# MAX_M10M_PINOUT.net
KiCad netlist of a schematic drawn in Altium Designer
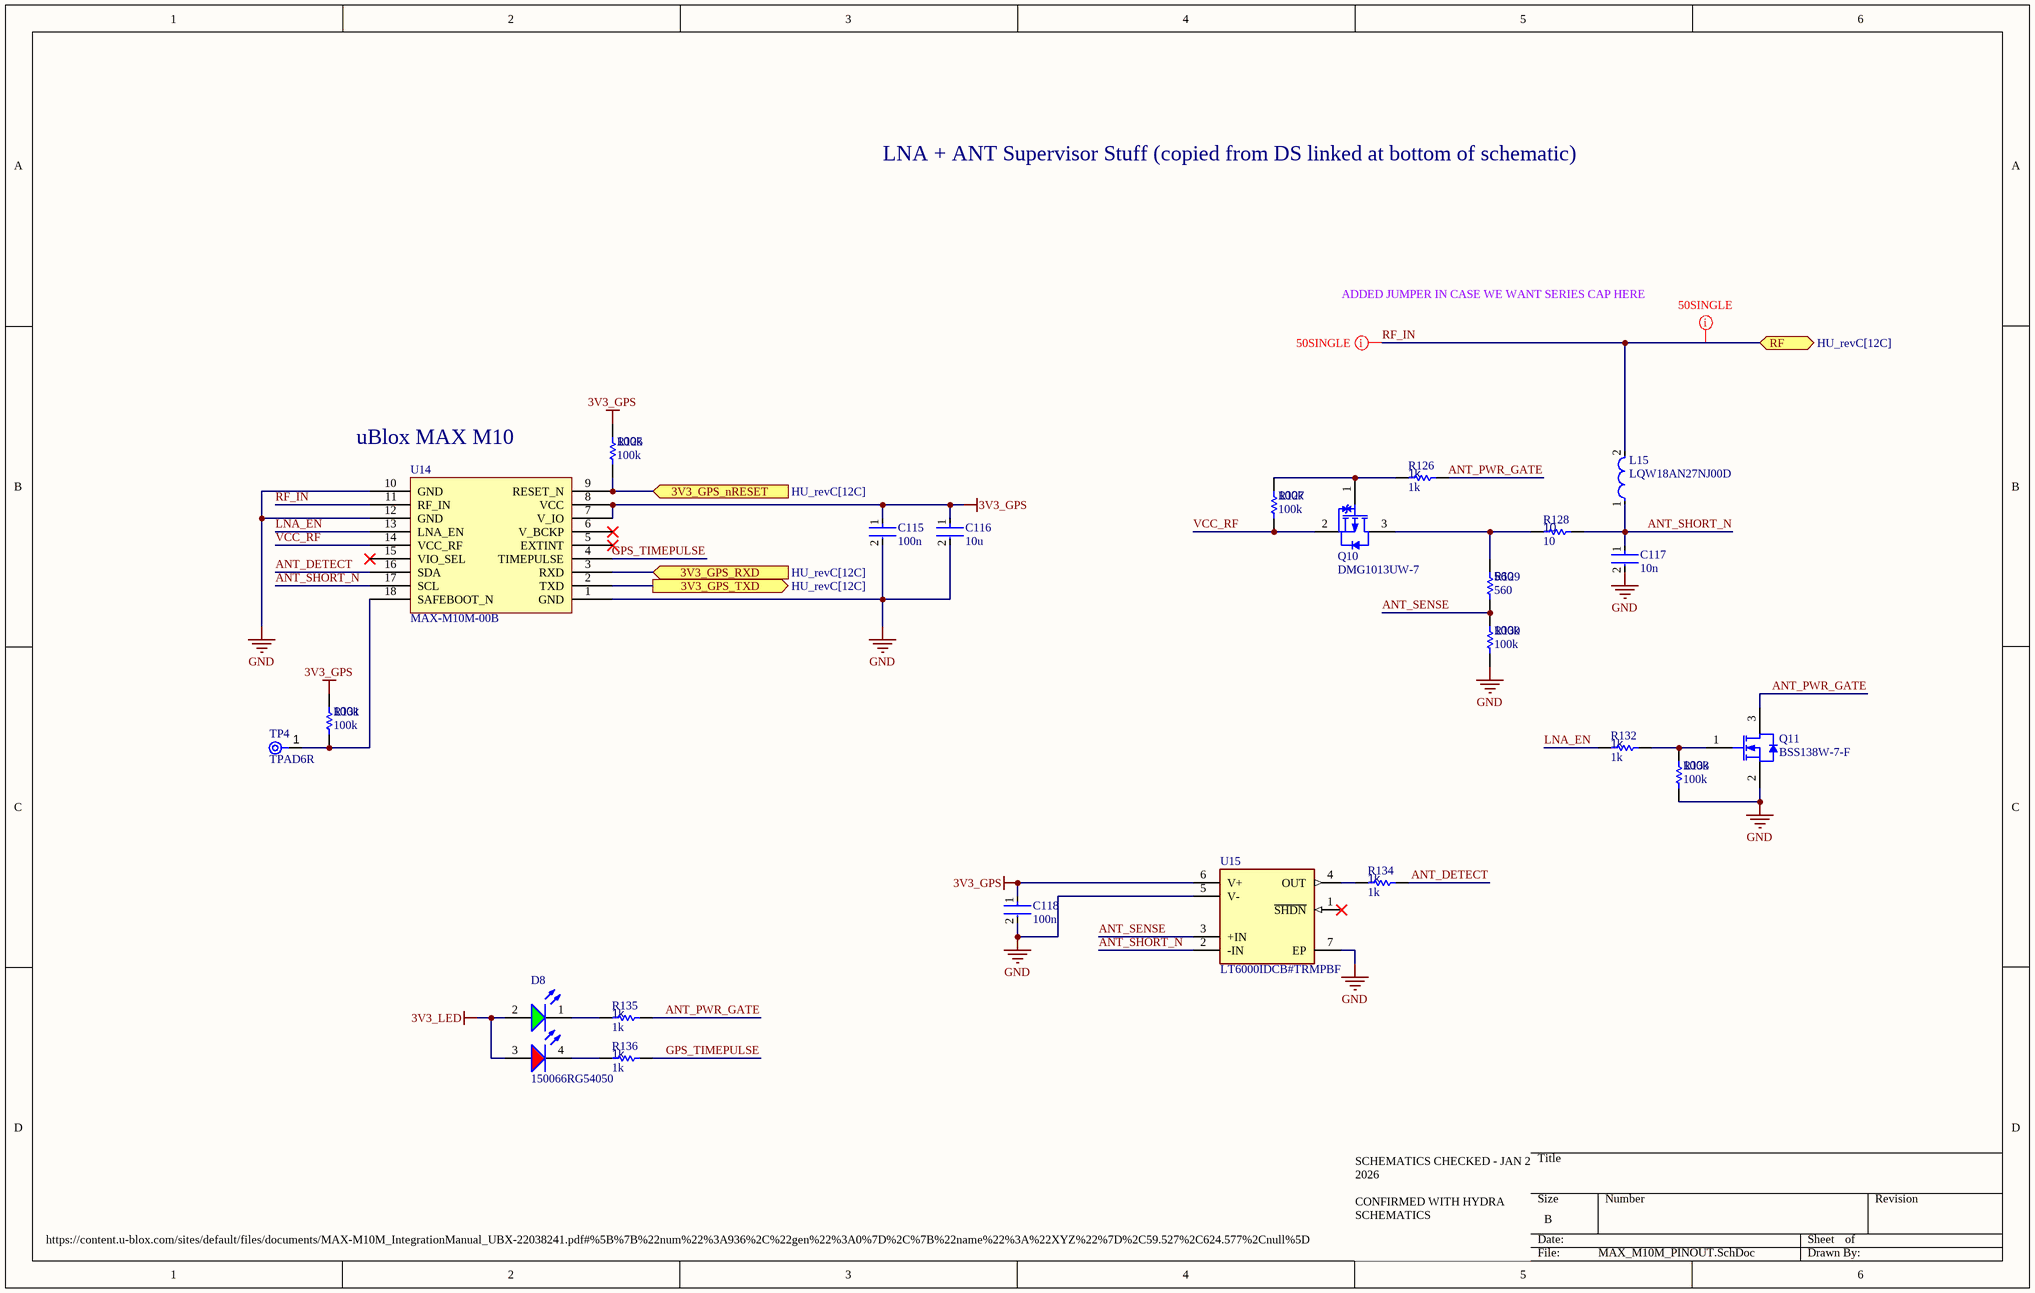
[diagram p0: MAX_M10M_PINOUT.SchDoc]

(export (version "E")
  (design (tool "Eeschema 10.0.6"))
  (components
    (comp (ref "C115")
      (value "100n")
      (footprint "FP-0402-L_1_0_0_05-W_0_5-IPC_A")
      (description "LARGE PADS, 0402 CAP, CHANGE COMMENT TO MATCH REAL P/N")
      (libsource (lib "Space Concordia") (part "b4654b650e69147ec39a6b967a45e02"))
    )
    (comp (ref "C116")
      (value "10u")
      (footprint "FP-0402-L_1_0_0_05-W_0_5-IPC_A")
      (description "LARGE PADS, 0402 CAP, CHANGE COMMENT TO MATCH REAL P/N")
      (libsource (lib "Space Concordia") (part "b4654b650e69147ec39a6b967a45e02"))
    )
    (comp (ref "C117")
      (value "10n")
      (footprint "FP-0402-L_1_0_0_05-W_0_5-IPC_A")
      (description "LARGE PADS, 0402 CAP, CHANGE COMMENT TO MATCH REAL P/N")
      (libsource (lib "Space Concordia") (part "b4654b650e69147ec39a6b967a45e02"))
    )
    (comp (ref "C118")
      (value "100n")
      (footprint "FP-0402-L_1_0_0_05-W_0_5-IPC_A")
      (description "LARGE PADS, 0402 CAP, CHANGE COMMENT TO MATCH REAL P/N")
      (libsource (lib "Space Concordia") (part "b4654b650e69147ec39a6b967a45e02"))
    )
    (comp (ref "D8")
      (value "150066RG54050")
      (footprint "WL-SBCD_0606")
      (description "Led, Red/Grn, 180Mcd/230Mcd, 624Nm/525Nm Rohs Compliant: Yes")
      (fields (field (name "SOURCE") "rgled.SchLib"))
      (libsource (lib "Space Concordia") (part "CMP-004-00034-2"))
    )
    (comp (ref "L15")
      (value "LQW18AN27NJ00D")
      (footprint "FP-LQW18AN_00-MFG")
      (description "Wire Wound RF Inductor 27nH ±5% 440mA 0.21Ω 0603 (1608)")
      (fields (field (name "TOLERANCE") "5%"))
      (libsource (lib "Altium Content Vault") (part "725321dda6339637d4d059423bc1c3c"))
    )
    (comp (ref "Q10")
      (value "DMG1013UW-7")
      (footprint "DIOD-SOT323-3_V")
      (fields (field (name "MANUFACTURER") "Diodes Inc"))
      (libsource (lib "Altium Content Vault") (part "PEMOS-GSD-3_C"))
    )
    (comp (ref "Q11")
      (value "BSS138W-7-F")
      (footprint "DIOD-SOT323-3_V")
      (fields (field (name "MANUFACTURER") "DiodesIncorporated"))
      (libsource (lib "Altium Content Vault") (part "NEMOS-GSD-3"))
    )
    (comp (ref "R125")
      (value "100k")
      (footprint "R0603B")
      (description "Resistor")
      (fields (field (name "ALTIUM_VALUE") "100k"))
      (libsource (lib "Space Concordia") (part "Resistor"))
    )
    (comp (ref "R126")
      (value "1k")
      (footprint "R0603B")
      (description "Resistor")
      (fields (field (name "ALTIUM_VALUE") "1k"))
      (libsource (lib "Space Concordia") (part "Resistor"))
    )
    (comp (ref "R127")
      (value "100k")
      (footprint "R0603B")
      (description "Resistor")
      (fields (field (name "ALTIUM_VALUE") "100k"))
      (libsource (lib "Space Concordia") (part "Resistor"))
    )
    (comp (ref "R128")
      (value "10")
      (footprint "R0603B")
      (description "Resistor")
      (fields (field (name "ALTIUM_VALUE") "10"))
      (libsource (lib "Space Concordia") (part "Resistor"))
    )
    (comp (ref "R129")
      (value "560")
      (footprint "R0603B")
      (description "Resistor")
      (fields (field (name "ALTIUM_VALUE") "560"))
      (libsource (lib "Space Concordia") (part "Resistor"))
    )
    (comp (ref "R130")
      (value "100k")
      (footprint "R0603B")
      (description "Resistor")
      (fields (field (name "ALTIUM_VALUE") "100k"))
      (libsource (lib "Space Concordia") (part "Resistor"))
    )
    (comp (ref "R131")
      (value "100k")
      (footprint "R0603B")
      (description "Resistor")
      (fields (field (name "ALTIUM_VALUE") "100k"))
      (libsource (lib "Space Concordia") (part "Resistor"))
    )
    (comp (ref "R132")
      (value "1k")
      (footprint "R0603B")
      (description "Resistor")
      (fields (field (name "ALTIUM_VALUE") "1k"))
      (libsource (lib "Space Concordia") (part "Resistor"))
    )
    (comp (ref "R133")
      (value "100k")
      (footprint "R0603B")
      (description "Resistor")
      (fields (field (name "ALTIUM_VALUE") "100k"))
      (libsource (lib "Space Concordia") (part "Resistor"))
    )
    (comp (ref "R134")
      (value "1k")
      (footprint "R0603B")
      (description "Resistor")
      (fields (field (name "ALTIUM_VALUE") "1k"))
      (libsource (lib "Space Concordia") (part "Resistor"))
    )
    (comp (ref "R135")
      (value "1k")
      (footprint "R0603B")
      (description "Resistor")
      (fields (field (name "ALTIUM_VALUE") "1k"))
      (libsource (lib "Space Concordia") (part "Resistor"))
    )
    (comp (ref "R136")
      (value "1k")
      (footprint "R0603B")
      (description "Resistor")
      (fields (field (name "ALTIUM_VALUE") "1k"))
      (libsource (lib "Space Concordia") (part "Resistor"))
    )
    (comp (ref "TP4")
      (value "TPAD6R")
      (footprint "New footprint 1")
      (description "Test Point .6mm")
      (libsource (lib "Space Concordia") (part "TP"))
    )
    (comp (ref "U14")
      (value "MAX-M10M-00B")
      (footprint "MAX-M10M-00B-Footprint-1")
      (description "Gnss Lcc Rx Mod, Rom, Crystal")
      (libsource (lib "Space Concordia") (part "MAX-M10M-00B"))
    )
    (comp (ref "U15")
      (value "LT6000IDCB#TRMPBF")
      (footprint "FP-DCB-6-05-08-1715-MFG")
      (description "IC OPAMP GP 1 CIRCUIT 6DFN")
      (libsource (lib "Altium Content Vault") (part "33bb285994f2e703f79bf9d86341a8a"))
    )
  )
  (nets
    (net (code "1") (name "/3V3_GPS_RXD") (class "Default")
      (node (ref "U14") (pin "3") (pinfunction "RXD_3") (pintype "passive"))
    )
    (net (code "2") (name "/3V3_GPS_TXD") (class "Default")
      (node (ref "U14") (pin "2") (pinfunction "TXD_2") (pintype "passive"))
    )
    (net (code "3") (name "/3V3_GPS_nRESET") (class "Default")
      (node (ref "R125") (pin "2") (pinfunction "2_2") (pintype "passive"))
      (node (ref "U14") (pin "9") (pinfunction "RESET_N_9") (pintype "passive"))
    )
    (net (code "4") (name "/ANT_DETECT") (class "Default")
      (node (ref "R134") (pin "2") (pinfunction "2_2") (pintype "passive"))
      (node (ref "U14") (pin "16") (pinfunction "SDA_16") (pintype "passive"))
    )
    (net (code "5") (name "/ANT_PWR_GATE") (class "Default")
      (node (ref "Q11") (pin "3") (pinfunction "D_3") (pintype "passive"))
      (node (ref "R126") (pin "2") (pinfunction "2_2") (pintype "passive"))
      (node (ref "R135") (pin "1") (pinfunction "1_1") (pintype "passive"))
    )
    (net (code "6") (name "/ANT_SENSE") (class "Default")
      (node (ref "R129") (pin "2") (pinfunction "2_2") (pintype "passive"))
      (node (ref "R130") (pin "1") (pinfunction "1_1") (pintype "passive"))
      (node (ref "U15") (pin "3") (pinfunction "+IN_3") (pintype "tri_state"))
    )
    (net (code "7") (name "/ANT_SHORT_N") (class "Default")
      (node (ref "C117") (pin "1") (pinfunction "1_1") (pintype "passive"))
      (node (ref "L15") (pin "1") (pinfunction "1_1") (pintype "passive"))
      (node (ref "R128") (pin "2") (pinfunction "2_2") (pintype "passive"))
      (node (ref "U14") (pin "17") (pinfunction "SCL_17") (pintype "passive"))
      (node (ref "U15") (pin "2") (pinfunction "-IN_2") (pintype "tri_state"))
    )
    (net (code "8") (name "/GPS_TIMEPULSE") (class "Default")
      (node (ref "R136") (pin "1") (pinfunction "1_1") (pintype "passive"))
      (node (ref "U14") (pin "4") (pinfunction "TIMEPULSE_4") (pintype "passive"))
    )
    (net (code "9") (name "/LNA_EN") (class "Default")
      (node (ref "R132") (pin "1") (pinfunction "1_1") (pintype "passive"))
      (node (ref "U14") (pin "13") (pinfunction "LNA_EN_13") (pintype "passive"))
    )
    (net (code "10") (name "/RF_IN") (class "Default")
      (node (ref "L15") (pin "2") (pinfunction "2_2") (pintype "passive"))
      (node (ref "U14") (pin "11") (pinfunction "RF_IN_11") (pintype "passive"))
    )
    (net (code "11") (name "/VCC_RF") (class "Default")
      (node (ref "Q10") (pin "2") (pinfunction "S_2") (pintype "passive"))
      (node (ref "R127") (pin "2") (pinfunction "2_2") (pintype "passive"))
      (node (ref "U14") (pin "14") (pinfunction "VCC_RF_14") (pintype "passive"))
    )
    (net (code "12") (name "3V3_GPS") (class "Default")
      (node (ref "C115") (pin "1") (pinfunction "1_1") (pintype "passive"))
      (node (ref "C116") (pin "1") (pinfunction "1_1") (pintype "passive"))
      (node (ref "C118") (pin "1") (pinfunction "1_1") (pintype "passive"))
      (node (ref "R125") (pin "1") (pinfunction "1_1") (pintype "passive"))
      (node (ref "R131") (pin "1") (pinfunction "1_1") (pintype "passive"))
      (node (ref "U14") (pin "7") (pinfunction "V_IO_7") (pintype "passive"))
      (node (ref "U14") (pin "8") (pinfunction "VCC_8") (pintype "passive"))
      (node (ref "U15") (pin "6") (pinfunction "V+_6") (pintype "power_in"))
    )
    (net (code "13") (name "3V3_LED") (class "Default")
      (node (ref "D8") (pin "2") (pinfunction "A_2") (pintype "passive"))
      (node (ref "D8") (pin "3") (pinfunction "A_3") (pintype "passive"))
    )
    (net (code "14") (name "GND") (class "Default")
      (node (ref "C115") (pin "2") (pinfunction "2_2") (pintype "passive"))
      (node (ref "C116") (pin "2") (pinfunction "2_2") (pintype "passive"))
      (node (ref "C117") (pin "2") (pinfunction "2_2") (pintype "passive"))
      (node (ref "C118") (pin "2") (pinfunction "2_2") (pintype "passive"))
      (node (ref "Q11") (pin "2") (pinfunction "S_2") (pintype "passive"))
      (node (ref "R130") (pin "2") (pinfunction "2_2") (pintype "passive"))
      (node (ref "R133") (pin "2") (pinfunction "2_2") (pintype "passive"))
      (node (ref "U14") (pin "1") (pinfunction "GND_1") (pintype "passive"))
      (node (ref "U14") (pin "10") (pinfunction "GND_10") (pintype "passive"))
      (node (ref "U14") (pin "12") (pinfunction "GND_12") (pintype "passive"))
      (node (ref "U15") (pin "5") (pinfunction "V-_5") (pintype "power_in"))
      (node (ref "U15") (pin "7") (pinfunction "EP_7") (pintype "power_in"))
    )
    (net (code "15") (name "Net-(D8-K-Pad1)") (class "Default")
      (node (ref "D8") (pin "1") (pinfunction "K_1") (pintype "passive"))
      (node (ref "R135") (pin "2") (pinfunction "2_2") (pintype "passive"))
    )
    (net (code "16") (name "Net-(D8-K-Pad4)") (class "Default")
      (node (ref "D8") (pin "4") (pinfunction "K_4") (pintype "passive"))
      (node (ref "R136") (pin "2") (pinfunction "2_2") (pintype "passive"))
    )
    (net (code "17") (name "Net-(Q10-D)") (class "Default")
      (node (ref "Q10") (pin "3") (pinfunction "D_3") (pintype "passive"))
      (node (ref "R128") (pin "1") (pinfunction "1_1") (pintype "passive"))
      (node (ref "R129") (pin "1") (pinfunction "1_1") (pintype "passive"))
    )
    (net (code "18") (name "Net-(Q10-G)") (class "Default")
      (node (ref "Q10") (pin "1") (pinfunction "G_1") (pintype "passive"))
      (node (ref "R126") (pin "1") (pinfunction "1_1") (pintype "passive"))
      (node (ref "R127") (pin "1") (pinfunction "1_1") (pintype "passive"))
    )
    (net (code "19") (name "Net-(Q11-G)") (class "Default")
      (node (ref "Q11") (pin "1") (pinfunction "G_1") (pintype "passive"))
      (node (ref "R132") (pin "2") (pinfunction "2_2") (pintype "passive"))
      (node (ref "R133") (pin "1") (pinfunction "1_1") (pintype "passive"))
    )
    (net (code "20") (name "Net-(TP4-TP)") (class "Default")
      (node (ref "R131") (pin "2") (pinfunction "2_2") (pintype "passive"))
      (node (ref "TP4") (pin "1") (pinfunction "TP_1") (pintype "passive"))
      (node (ref "U14") (pin "18") (pinfunction "SAFEBOOT_N_18") (pintype "passive"))
    )
    (net (code "21") (name "Net-(U15-OUT)") (class "Default")
      (node (ref "R134") (pin "1") (pinfunction "1_1") (pintype "passive"))
      (node (ref "U15") (pin "4") (pinfunction "OUT_4") (pintype "output"))
    )
    (net (code "22") (name "unconnected-(U14-EXTINT-Pad5)") (class "Default")
      (node (ref "U14") (pin "5") (pinfunction "EXTINT_5") (pintype "passive+no_connect"))
    )
    (net (code "23") (name "unconnected-(U14-VIO_SEL-Pad15)") (class "Default")
      (node (ref "U14") (pin "15") (pinfunction "VIO_SEL_15") (pintype "passive+no_connect"))
    )
    (net (code "24") (name "unconnected-(U14-V_BCKP-Pad6)") (class "Default")
      (node (ref "U14") (pin "6") (pinfunction "V_BCKP_6") (pintype "passive+no_connect"))
    )
    (net (code "25") (name "unconnected-(U15-~{SHDN}-Pad1)") (class "Default")
      (node (ref "U15") (pin "1") (pinfunction "~{SHDN}_1") (pintype "input+no_connect"))
    )
  )
)
